# KeyboardControl.net
KiCad netlist of a schematic drawn in Altium Designer
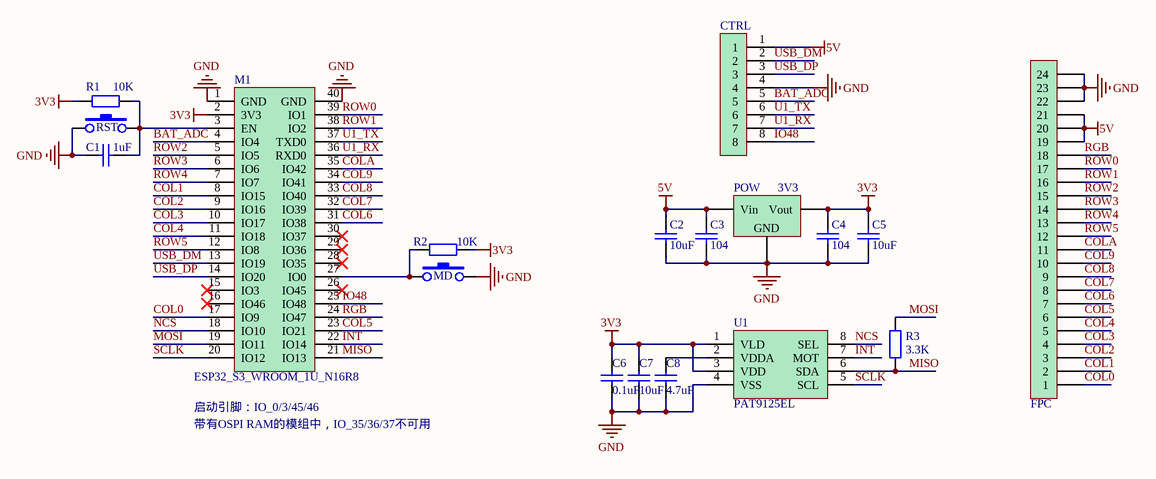
[diagram p0: KeyboardControl.SchDoc]

(export (version "E")
  (design (tool "Eeschema 10.0.6"))
  (components
    (comp (ref "C1")
      (value "1uF")
      (footprint "0603")
      (description "贴片电容 0603")
      (libsource (lib "MT_Device") (part "CAP_0603"))
    )
    (comp (ref "C2")
      (value "10uF")
      (footprint "0603")
      (description "贴片电容 0603")
      (libsource (lib "MT_Device") (part "CAP_0603"))
    )
    (comp (ref "C3")
      (value "104")
      (footprint "0603")
      (description "贴片电容 0603")
      (libsource (lib "MT_Device") (part "CAP_0603"))
    )
    (comp (ref "C4")
      (value "104")
      (footprint "0603")
      (description "贴片电容 0603")
      (libsource (lib "MT_Device") (part "CAP_0603"))
    )
    (comp (ref "C5")
      (value "10uF")
      (footprint "0603")
      (description "贴片电容 0603")
      (libsource (lib "MT_Device") (part "CAP_0603"))
    )
    (comp (ref "C6")
      (value "0.1uF")
      (footprint "0603")
      (description "贴片电容 0603")
      (libsource (lib "MT_Device") (part "CAP_0603"))
    )
    (comp (ref "C7")
      (value "10uF")
      (footprint "0603")
      (description "贴片电容 0603")
      (libsource (lib "MT_Device") (part "CAP_0603"))
    )
    (comp (ref "C8")
      (value "4.7uF")
      (footprint "0603")
      (description "贴片电容 0603")
      (libsource (lib "MT_Device") (part "CAP_0603"))
    )
    (comp (ref "CTRL")
      (value "SH1.25mm_8P")
      (footprint "SH1.25MM_8P")
      (description "SH")
      (libsource (lib "MT_Connector") (part "SH1.25mm_8P"))
    )
    (comp (ref "FPC")
      (value "FPC_0.5_24P")
      (footprint "FPC_0.5_24PIN")
      (description "FPC 0.5 24Pin")
      (libsource (lib "MT_Connector") (part "FPC_0.5_24P"))
    )
    (comp (ref "M1")
      (value "ESP32_S3_WROOM_1U_N16R8")
      (footprint "ESP32_S3_WROOM_1U")
      (description "ESP32 S3模组")
      (libsource (lib "MT_Module") (part "ESP32_S3_WROOM_1U"))
    )
    (comp (ref "MD")
      (value "KEY")
      (footprint "KEY_SMT_4_L")
      (description "卧式贴片按键 2*4*3.5mm")
      (libsource (lib "MT_Device") (part "KEY_SMT_4_L"))
    )
    (comp (ref "POW")
      (value "3V3")
      (footprint "SOT223")
      (description "线性稳压器")
      (libsource (lib "MT_Device") (part "LDO_AMS1117"))
    )
    (comp (ref "R1")
      (value "10K")
      (footprint "R_0603")
      (description "电阻 0603")
      (libsource (lib "MT_Device") (part "RES_0603"))
    )
    (comp (ref "R2")
      (value "10K")
      (footprint "R_0603")
      (description "电阻 0603")
      (libsource (lib "MT_Device") (part "RES_0603"))
    )
    (comp (ref "R3")
      (value "3.3K")
      (footprint "R_0603")
      (description "电阻 0603")
      (libsource (lib "") (part "RES_0603_1"))
    )
    (comp (ref "RST")
      (value "KEY")
      (footprint "KEY_SMT_4_L")
      (description "卧式贴片按键 2*4*3.5mm")
      (libsource (lib "MT_Device") (part "KEY_SMT_4_L"))
    )
    (comp (ref "U1")
      (value "PAT9125EL")
      (footprint "PAT9125EL")
      (description "Optical Tracking Miniature Chip")
      (libsource (lib "MT_Chip") (part "PAT9125EL"))
    )
  )
  (nets
    (net (code "1") (name "/BAT_ADC") (class "Default")
      (node (ref "CTRL") (pin "5") (pinfunction "5_5") (pintype "passive"))
      (node (ref "M1") (pin "4") (pinfunction "IO4_4") (pintype "passive"))
    )
    (net (code "2") (name "/COL0") (class "Default")
      (node (ref "FPC") (pin "1") (pinfunction "1_1") (pintype "passive"))
      (node (ref "M1") (pin "17") (pinfunction "IO9_17") (pintype "passive"))
    )
    (net (code "3") (name "/COL1") (class "Default")
      (node (ref "FPC") (pin "2") (pinfunction "2_2") (pintype "passive"))
      (node (ref "M1") (pin "8") (pinfunction "IO15_8") (pintype "passive"))
    )
    (net (code "4") (name "/COL2") (class "Default")
      (node (ref "FPC") (pin "3") (pinfunction "3_3") (pintype "passive"))
      (node (ref "M1") (pin "9") (pinfunction "IO16_9") (pintype "passive"))
    )
    (net (code "5") (name "/COL3") (class "Default")
      (node (ref "FPC") (pin "4") (pinfunction "4_4") (pintype "passive"))
      (node (ref "M1") (pin "10") (pinfunction "IO17_10") (pintype "passive"))
    )
    (net (code "6") (name "/COL4") (class "Default")
      (node (ref "FPC") (pin "5") (pinfunction "5_5") (pintype "passive"))
      (node (ref "M1") (pin "11") (pinfunction "IO18_11") (pintype "passive"))
    )
    (net (code "7") (name "/COL5") (class "Default")
      (node (ref "FPC") (pin "6") (pinfunction "6_6") (pintype "passive"))
      (node (ref "M1") (pin "23") (pinfunction "IO21_23") (pintype "passive"))
    )
    (net (code "8") (name "/COL6") (class "Default")
      (node (ref "FPC") (pin "7") (pinfunction "7_7") (pintype "passive"))
      (node (ref "M1") (pin "31") (pinfunction "IO38_31") (pintype "passive"))
    )
    (net (code "9") (name "/COL7") (class "Default")
      (node (ref "FPC") (pin "8") (pinfunction "8_8") (pintype "passive"))
      (node (ref "M1") (pin "32") (pinfunction "IO39_32") (pintype "passive"))
    )
    (net (code "10") (name "/COL8") (class "Default")
      (node (ref "FPC") (pin "9") (pinfunction "9_9") (pintype "passive"))
      (node (ref "M1") (pin "33") (pinfunction "IO40_33") (pintype "passive"))
    )
    (net (code "11") (name "/COL9") (class "Default")
      (node (ref "FPC") (pin "10") (pinfunction "10_10") (pintype "passive"))
      (node (ref "M1") (pin "34") (pinfunction "IO41_34") (pintype "passive"))
    )
    (net (code "12") (name "/COLA") (class "Default")
      (node (ref "FPC") (pin "11") (pinfunction "11_11") (pintype "passive"))
      (node (ref "M1") (pin "35") (pinfunction "IO42_35") (pintype "passive"))
    )
    (net (code "13") (name "/INT") (class "Default")
      (node (ref "M1") (pin "22") (pinfunction "IO14_22") (pintype "passive"))
      (node (ref "U1") (pin "7") (pinfunction "MOT_7") (pintype "passive"))
    )
    (net (code "14") (name "/IO48") (class "Default")
      (node (ref "CTRL") (pin "8") (pinfunction "8_8") (pintype "passive"))
      (node (ref "M1") (pin "25") (pinfunction "IO48_25") (pintype "passive"))
    )
    (net (code "15") (name "/MISO") (class "Default")
      (node (ref "M1") (pin "21") (pinfunction "IO13_21") (pintype "passive"))
      (node (ref "R3") (pin "1") (pinfunction "1_1") (pintype "passive"))
      (node (ref "U1") (pin "6") (pinfunction "SDA_6") (pintype "passive"))
    )
    (net (code "16") (name "/MOSI") (class "Default")
      (node (ref "M1") (pin "19") (pinfunction "IO11_19") (pintype "passive"))
      (node (ref "R3") (pin "2") (pinfunction "2_2") (pintype "passive"))
    )
    (net (code "17") (name "/NCS") (class "Default")
      (node (ref "M1") (pin "18") (pinfunction "IO10_18") (pintype "passive"))
      (node (ref "U1") (pin "8") (pinfunction "SEL_8") (pintype "passive"))
    )
    (net (code "18") (name "/RGB") (class "Default")
      (node (ref "FPC") (pin "18") (pinfunction "18_18") (pintype "passive"))
      (node (ref "M1") (pin "24") (pinfunction "IO47_24") (pintype "passive"))
    )
    (net (code "19") (name "/ROW0") (class "Default")
      (node (ref "FPC") (pin "17") (pinfunction "17_17") (pintype "passive"))
      (node (ref "M1") (pin "39") (pinfunction "IO1_39") (pintype "passive"))
    )
    (net (code "20") (name "/ROW1") (class "Default")
      (node (ref "FPC") (pin "16") (pinfunction "16_16") (pintype "passive"))
      (node (ref "M1") (pin "38") (pinfunction "IO2_38") (pintype "passive"))
    )
    (net (code "21") (name "/ROW2") (class "Default")
      (node (ref "FPC") (pin "15") (pinfunction "15_15") (pintype "passive"))
      (node (ref "M1") (pin "5") (pinfunction "IO5_5") (pintype "passive"))
    )
    (net (code "22") (name "/ROW3") (class "Default")
      (node (ref "FPC") (pin "14") (pinfunction "14_14") (pintype "passive"))
      (node (ref "M1") (pin "6") (pinfunction "IO6_6") (pintype "passive"))
    )
    (net (code "23") (name "/ROW4") (class "Default")
      (node (ref "FPC") (pin "13") (pinfunction "13_13") (pintype "passive"))
      (node (ref "M1") (pin "7") (pinfunction "IO7_7") (pintype "passive"))
    )
    (net (code "24") (name "/ROW5") (class "Default")
      (node (ref "FPC") (pin "12") (pinfunction "12_12") (pintype "passive"))
      (node (ref "M1") (pin "12") (pinfunction "IO8_12") (pintype "passive"))
    )
    (net (code "25") (name "/SCLK") (class "Default")
      (node (ref "M1") (pin "20") (pinfunction "IO12_20") (pintype "passive"))
      (node (ref "U1") (pin "5") (pinfunction "SCL_5") (pintype "passive"))
    )
    (net (code "26") (name "/U1_RX") (class "Default")
      (node (ref "CTRL") (pin "7") (pinfunction "7_7") (pintype "passive"))
      (node (ref "M1") (pin "36") (pinfunction "RXD0_36") (pintype "passive"))
    )
    (net (code "27") (name "/U1_TX") (class "Default")
      (node (ref "CTRL") (pin "6") (pinfunction "6_6") (pintype "passive"))
      (node (ref "M1") (pin "37") (pinfunction "TXD0_37") (pintype "passive"))
    )
    (net (code "28") (name "/USB_DM") (class "Default")
      (node (ref "CTRL") (pin "2") (pinfunction "2_2") (pintype "passive"))
      (node (ref "M1") (pin "13") (pinfunction "IO19_13") (pintype "passive"))
    )
    (net (code "29") (name "/USB_DP") (class "Default")
      (node (ref "CTRL") (pin "3") (pinfunction "3_3") (pintype "passive"))
      (node (ref "M1") (pin "14") (pinfunction "IO20_14") (pintype "passive"))
    )
    (net (code "30") (name "3V3") (class "Default")
      (node (ref "C4") (pin "2") (pinfunction "2_2") (pintype "passive"))
      (node (ref "C5") (pin "2") (pinfunction "2_2") (pintype "passive"))
      (node (ref "C6") (pin "2") (pinfunction "2_2") (pintype "passive"))
      (node (ref "C7") (pin "2") (pinfunction "2_2") (pintype "passive"))
      (node (ref "M1") (pin "2") (pinfunction "3V3_2") (pintype "passive"))
      (node (ref "POW") (pin "2") (pinfunction "Vout_2") (pintype "passive"))
      (node (ref "R1") (pin "2") (pinfunction "2_2") (pintype "passive"))
      (node (ref "R2") (pin "1") (pinfunction "1_1") (pintype "passive"))
      (node (ref "U1") (pin "1") (pinfunction "VLD_1") (pintype "passive"))
      (node (ref "U1") (pin "3") (pinfunction "VDD_3") (pintype "passive"))
    )
    (net (code "31") (name "5V") (class "Default")
      (node (ref "C2") (pin "2") (pinfunction "2_2") (pintype "passive"))
      (node (ref "C3") (pin "2") (pinfunction "2_2") (pintype "passive"))
      (node (ref "CTRL") (pin "1") (pinfunction "1_1") (pintype "passive"))
      (node (ref "FPC") (pin "19") (pinfunction "19_19") (pintype "passive"))
      (node (ref "FPC") (pin "20") (pinfunction "20_20") (pintype "passive"))
      (node (ref "FPC") (pin "21") (pinfunction "21_21") (pintype "passive"))
      (node (ref "POW") (pin "3") (pinfunction "Vin_3") (pintype "passive"))
    )
    (net (code "32") (name "GND") (class "Default")
      (node (ref "C1") (pin "1") (pinfunction "1_1") (pintype "passive"))
      (node (ref "C2") (pin "1") (pinfunction "1_1") (pintype "passive"))
      (node (ref "C3") (pin "1") (pinfunction "1_1") (pintype "passive"))
      (node (ref "C4") (pin "1") (pinfunction "1_1") (pintype "passive"))
      (node (ref "C5") (pin "1") (pinfunction "1_1") (pintype "passive"))
      (node (ref "C6") (pin "1") (pinfunction "1_1") (pintype "passive"))
      (node (ref "C7") (pin "1") (pinfunction "1_1") (pintype "passive"))
      (node (ref "C8") (pin "1") (pinfunction "1_1") (pintype "passive"))
      (node (ref "CTRL") (pin "4") (pinfunction "4_4") (pintype "passive"))
      (node (ref "FPC") (pin "22") (pinfunction "22_22") (pintype "passive"))
      (node (ref "FPC") (pin "23") (pinfunction "23_23") (pintype "passive"))
      (node (ref "FPC") (pin "24") (pinfunction "24_24") (pintype "passive"))
      (node (ref "M1") (pin "1") (pinfunction "GND_1") (pintype "passive"))
      (node (ref "M1") (pin "40") (pinfunction "GND_40") (pintype "passive"))
      (node (ref "MD") (pin "2") (pinfunction "2_2") (pintype "passive"))
      (node (ref "POW") (pin "1") (pinfunction "GND_1") (pintype "passive"))
      (node (ref "RST") (pin "1") (pinfunction "1_1") (pintype "passive"))
      (node (ref "U1") (pin "4") (pinfunction "VSS_4") (pintype "passive"))
    )
    (net (code "33") (name "Net-(M1-EN)") (class "Default")
      (node (ref "C1") (pin "2") (pinfunction "2_2") (pintype "passive"))
      (node (ref "M1") (pin "3") (pinfunction "EN_3") (pintype "passive"))
      (node (ref "R1") (pin "1") (pinfunction "1_1") (pintype "passive"))
      (node (ref "RST") (pin "2") (pinfunction "2_2") (pintype "passive"))
    )
    (net (code "34") (name "Net-(M1-IO0)") (class "Default")
      (node (ref "M1") (pin "27") (pinfunction "IO0_27") (pintype "passive"))
      (node (ref "MD") (pin "1") (pinfunction "1_1") (pintype "passive"))
      (node (ref "R2") (pin "2") (pinfunction "2_2") (pintype "passive"))
    )
    (net (code "35") (name "Net-(U1-VDDA)") (class "Default")
      (node (ref "C8") (pin "2") (pinfunction "2_2") (pintype "passive"))
      (node (ref "U1") (pin "2") (pinfunction "VDDA_2") (pintype "passive"))
    )
    (net (code "36") (name "unconnected-(M1-IO3-Pad15)") (class "Default")
      (node (ref "M1") (pin "15") (pinfunction "IO3_15") (pintype "passive+no_connect"))
    )
    (net (code "37") (name "unconnected-(M1-IO35-Pad28)") (class "Default")
      (node (ref "M1") (pin "28") (pinfunction "IO35_28") (pintype "passive+no_connect"))
    )
    (net (code "38") (name "unconnected-(M1-IO36-Pad29)") (class "Default")
      (node (ref "M1") (pin "29") (pinfunction "IO36_29") (pintype "passive+no_connect"))
    )
    (net (code "39") (name "unconnected-(M1-IO37-Pad30)") (class "Default")
      (node (ref "M1") (pin "30") (pinfunction "IO37_30") (pintype "passive+no_connect"))
    )
    (net (code "40") (name "unconnected-(M1-IO45-Pad26)") (class "Default")
      (node (ref "M1") (pin "26") (pinfunction "IO45_26") (pintype "passive+no_connect"))
    )
    (net (code "41") (name "unconnected-(M1-IO46-Pad16)") (class "Default")
      (node (ref "M1") (pin "16") (pinfunction "IO46_16") (pintype "passive+no_connect"))
    )
  )
)
